# Sheet2.net
KiCad netlist of a schematic drawn in Altium Designer
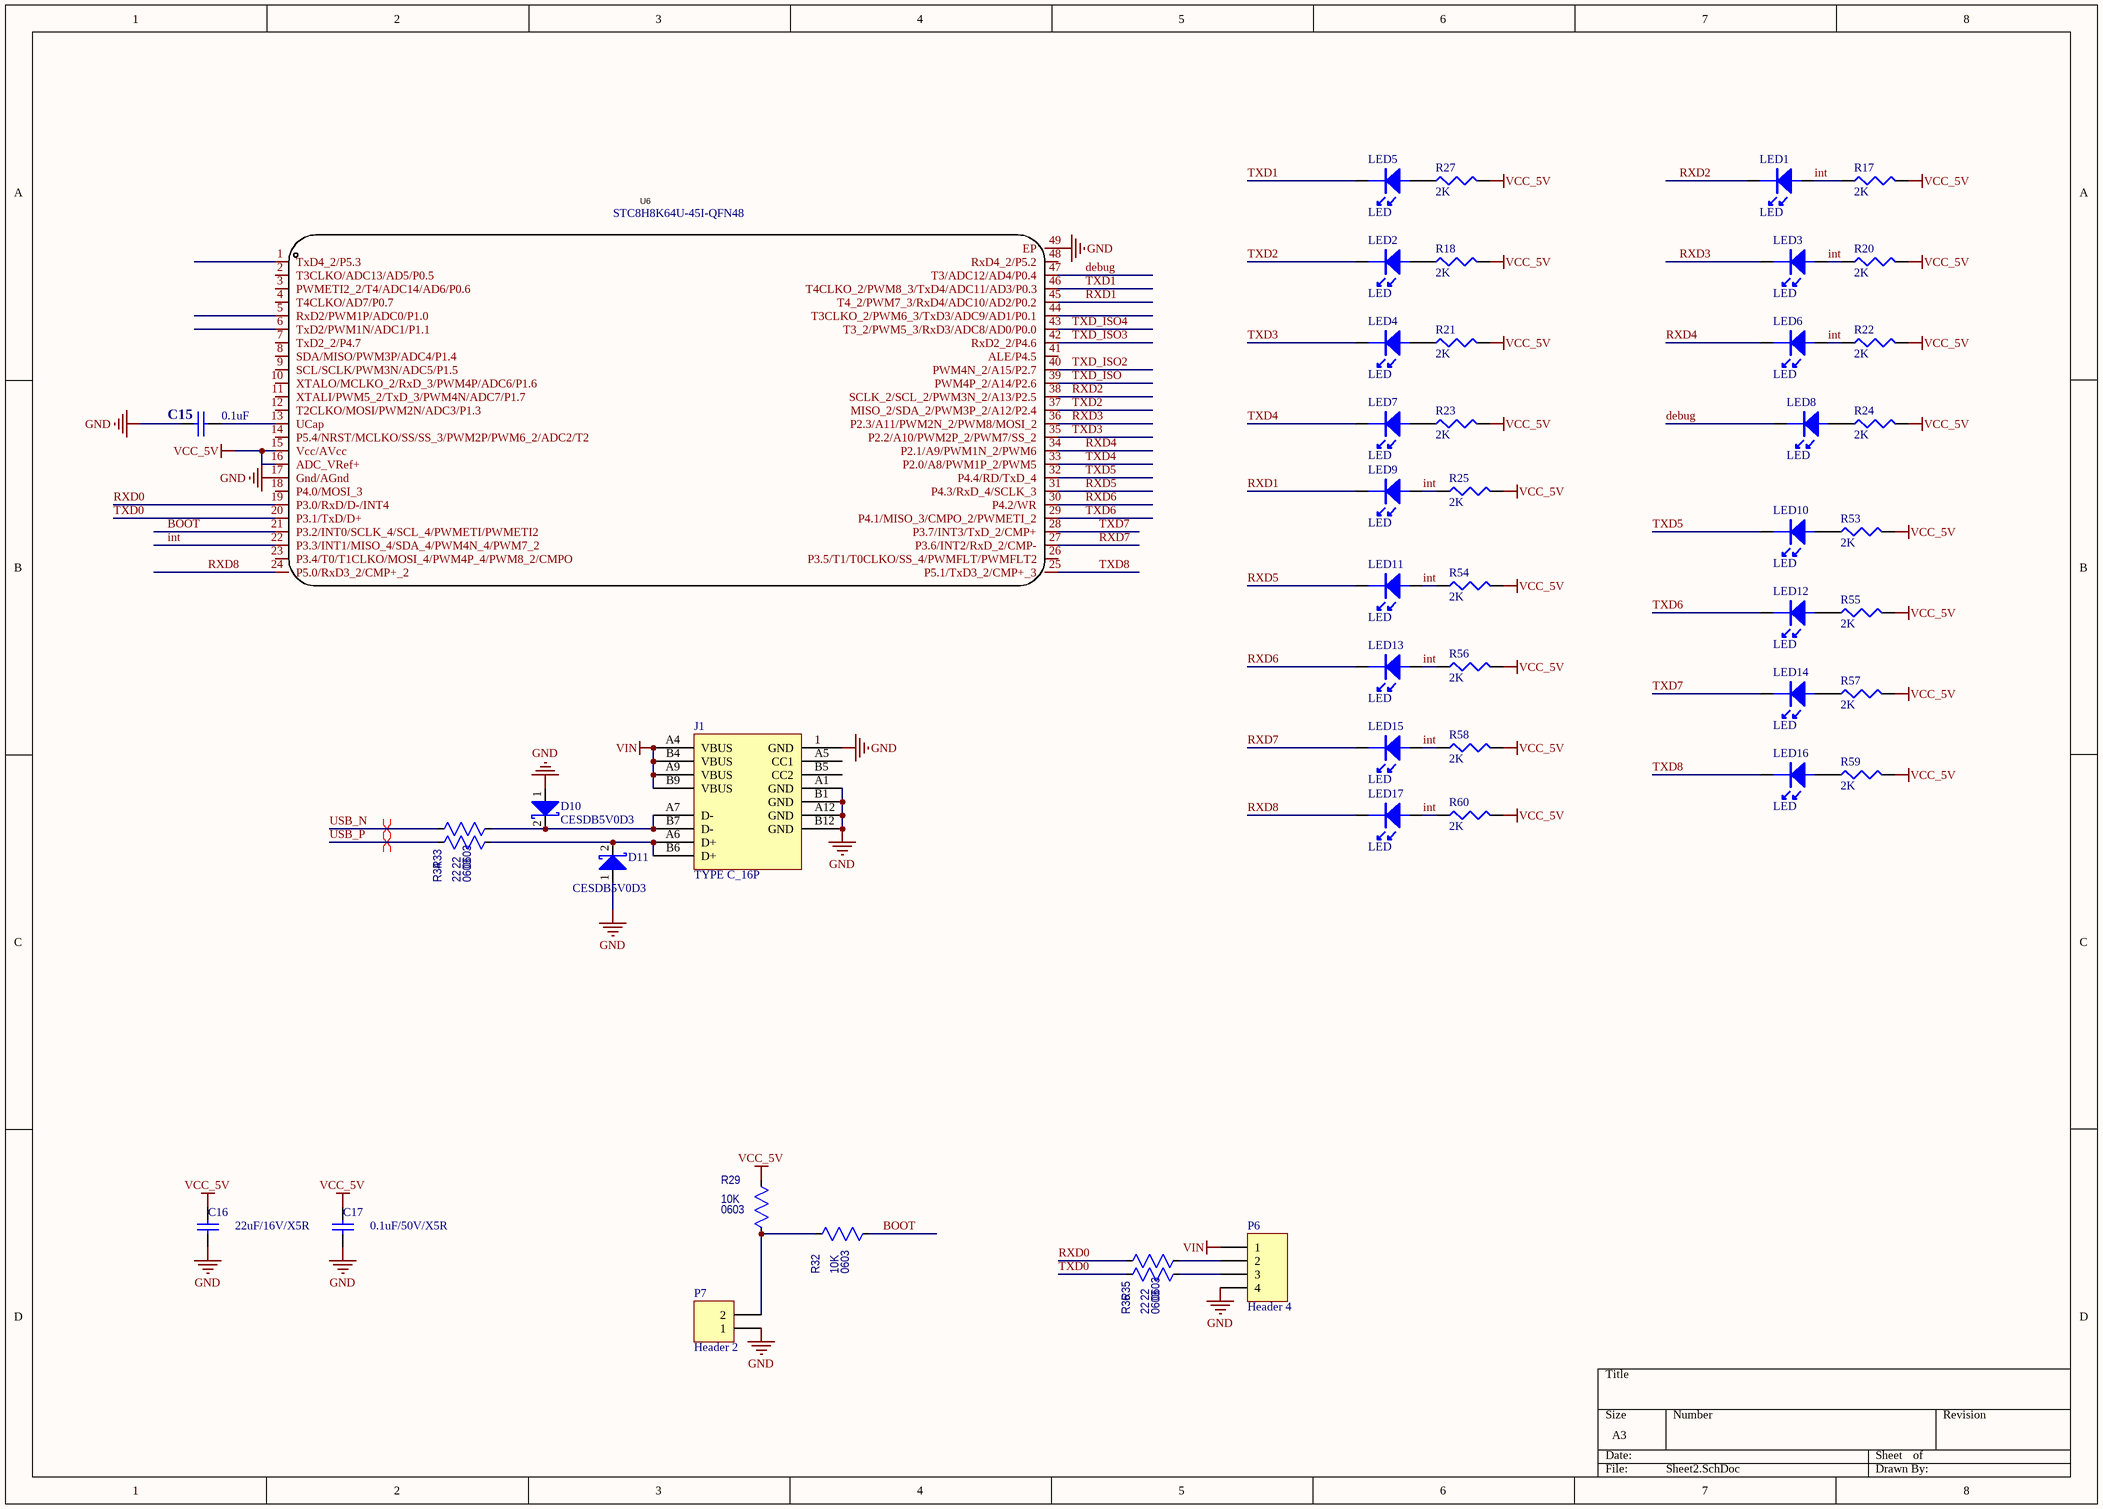
[diagram p0: Sheet2.SchDoc]

(export (version "E")
  (design (tool "Eeschema 10.0.6"))
  (components
    (comp (ref "C15")
      (value "0.1uF")
      (footprint "0603C")
      (description "Capacitor")
      (libsource (lib "*") (part "CAP"))
    )
    (comp (ref "C16")
      (value "22uF/16V/X5R")
      (footprint "0805C")
      (description "贴片电容 20%")
      (libsource (lib "XiaoyI") (part "CAP4"))
    )
    (comp (ref "C17")
      (value "0.1uF/50V/X5R")
      (footprint "0603C")
      (description "贴片电容 20%")
      (libsource (lib "XiaoyI") (part "CAP4"))
    )
    (comp (ref "D10")
      (value "CESDB5V0D3")
      (footprint "SOD323")
      (description "Schottky Diode")
      (libsource (lib "*") (part "DIODE S"))
    )
    (comp (ref "D11")
      (value "CESDB5V0D3")
      (footprint "SOD323")
      (description "Schottky Diode")
      (libsource (lib "*") (part "DIODE S"))
    )
    (comp (ref "J1")
      (value "TYPE C_16P")
      (footprint "TYPEC_16P")
      (libsource (lib "Schlib_20110825") (part "TYPE C_16P"))
    )
    (comp (ref "LED1") (value "LED") (footprint "0603LED") (libsource (lib "我的元件库") (part "LED")))
    (comp (ref "LED2") (value "LED") (footprint "0603LED") (libsource (lib "我的元件库") (part "LED")))
    (comp (ref "LED3") (value "LED") (footprint "0603LED") (libsource (lib "我的元件库") (part "LED")))
    (comp (ref "LED4") (value "LED") (footprint "0603LED") (libsource (lib "我的元件库") (part "LED")))
    (comp (ref "LED5") (value "LED") (footprint "0603LED") (libsource (lib "我的元件库") (part "LED")))
    (comp (ref "LED6") (value "LED") (footprint "0603LED") (libsource (lib "我的元件库") (part "LED")))
    (comp (ref "LED7") (value "LED") (footprint "0603LED") (libsource (lib "我的元件库") (part "LED")))
    (comp (ref "LED8") (value "LED") (footprint "0603LED") (libsource (lib "我的元件库") (part "LED")))
    (comp (ref "LED9") (value "LED") (footprint "0603LED") (libsource (lib "我的元件库") (part "LED")))
    (comp (ref "LED10") (value "LED") (footprint "0603LED") (libsource (lib "我的元件库") (part "LED")))
    (comp (ref "LED11") (value "LED") (footprint "0603LED") (libsource (lib "我的元件库") (part "LED")))
    (comp (ref "LED12") (value "LED") (footprint "0603LED") (libsource (lib "我的元件库") (part "LED")))
    (comp (ref "LED13") (value "LED") (footprint "0603LED") (libsource (lib "我的元件库") (part "LED")))
    (comp (ref "LED14") (value "LED") (footprint "0603LED") (libsource (lib "我的元件库") (part "LED")))
    (comp (ref "LED15") (value "LED") (footprint "0603LED") (libsource (lib "我的元件库") (part "LED")))
    (comp (ref "LED16") (value "LED") (footprint "0603LED") (libsource (lib "我的元件库") (part "LED")))
    (comp (ref "LED17") (value "LED") (footprint "0603LED") (libsource (lib "我的元件库") (part "LED")))
    (comp (ref "P6")
      (value "Header 4")
      (footprint "HDR1X4")
      (description "Header, 4-Pin")
      (fields (field (name "PUBLISHER") "Altium Limited"))
      (libsource (lib "Miscellaneous Connectors") (part "Header 4"))
    )
    (comp (ref "P7")
      (value "Header 2")
      (footprint "HDR1X2")
      (description "Header, 2-Pin")
      (fields (field (name "PUBLISHER") "Altium Limited"))
      (libsource (lib "Miscellaneous Connectors") (part "Header 2"))
    )
    (comp (ref "R17")
      (value "2K")
      (footprint "0603R")
      (libsource (lib "ZWLIntegrated_Library") (part "RES1"))
    )
    (comp (ref "R18")
      (value "2K")
      (footprint "0603R")
      (libsource (lib "ZWLIntegrated_Library") (part "RES1"))
    )
    (comp (ref "R20")
      (value "2K")
      (footprint "0603R")
      (libsource (lib "ZWLIntegrated_Library") (part "RES1"))
    )
    (comp (ref "R21")
      (value "2K")
      (footprint "0603R")
      (libsource (lib "ZWLIntegrated_Library") (part "RES1"))
    )
    (comp (ref "R22")
      (value "2K")
      (footprint "0603R")
      (libsource (lib "ZWLIntegrated_Library") (part "RES1"))
    )
    (comp (ref "R23")
      (value "2K")
      (footprint "0603R")
      (libsource (lib "ZWLIntegrated_Library") (part "RES1"))
    )
    (comp (ref "R24")
      (value "2K")
      (footprint "0603R")
      (libsource (lib "ZWLIntegrated_Library") (part "RES1"))
    )
    (comp (ref "R25")
      (value "2K")
      (footprint "0603R")
      (libsource (lib "ZWLIntegrated_Library") (part "RES1"))
    )
    (comp (ref "R27")
      (value "2K")
      (footprint "0603R")
      (libsource (lib "ZWLIntegrated_Library") (part "RES1"))
    )
    (comp (ref "R29")
      (value "10K")
      (footprint "0603r")
      (fields
        (field (name "PARTNUMBER") "RC0603FR-071KL")
        (field (name "TOLERANCE") "tol")
        (field (name "PACKAGE") "0603")
        (field (name "Comment") "10k")
      )
      (libsource (lib "Karl") (part "Resistor_0603"))
    )
    (comp (ref "R32")
      (value "10K")
      (footprint "0603r")
      (fields
        (field (name "PARTNUMBER") "RC0603FR-071KL")
        (field (name "TOLERANCE") "tol")
        (field (name "PACKAGE") "0603")
        (field (name "Comment") "10k")
      )
      (libsource (lib "Karl") (part "Resistor_0603"))
    )
    (comp (ref "R33")
      (value "22")
      (footprint "0603r")
      (fields
        (field (name "PARTNUMBER") "RC0603FR-071KL")
        (field (name "TOLERANCE") "tol")
        (field (name "PACKAGE") "0603")
        (field (name "Comment") "10k")
      )
      (libsource (lib "Karl") (part "Resistor_0603"))
    )
    (comp (ref "R34")
      (value "22")
      (footprint "0603r")
      (fields
        (field (name "PARTNUMBER") "RC0603FR-071KL")
        (field (name "TOLERANCE") "tol")
        (field (name "PACKAGE") "0603")
        (field (name "Comment") "10k")
      )
      (libsource (lib "Karl") (part "Resistor_0603"))
    )
    (comp (ref "R35")
      (value "22")
      (footprint "0603r")
      (fields
        (field (name "PARTNUMBER") "RC0603FR-071KL")
        (field (name "TOLERANCE") "tol")
        (field (name "PACKAGE") "0603")
        (field (name "Comment") "10k")
      )
      (libsource (lib "Karl") (part "Resistor_0603"))
    )
    (comp (ref "R36")
      (value "22")
      (footprint "0603r")
      (fields
        (field (name "PARTNUMBER") "RC0603FR-071KL")
        (field (name "TOLERANCE") "tol")
        (field (name "PACKAGE") "0603")
        (field (name "Comment") "10k")
      )
      (libsource (lib "Karl") (part "Resistor_0603"))
    )
    (comp (ref "R53")
      (value "2K")
      (footprint "0603R")
      (libsource (lib "ZWLIntegrated_Library") (part "RES1"))
    )
    (comp (ref "R54")
      (value "2K")
      (footprint "0603R")
      (libsource (lib "ZWLIntegrated_Library") (part "RES1"))
    )
    (comp (ref "R55")
      (value "2K")
      (footprint "0603R")
      (libsource (lib "ZWLIntegrated_Library") (part "RES1"))
    )
    (comp (ref "R56")
      (value "2K")
      (footprint "0603R")
      (libsource (lib "ZWLIntegrated_Library") (part "RES1"))
    )
    (comp (ref "R57")
      (value "2K")
      (footprint "0603R")
      (libsource (lib "ZWLIntegrated_Library") (part "RES1"))
    )
    (comp (ref "R58")
      (value "2K")
      (footprint "0603R")
      (libsource (lib "ZWLIntegrated_Library") (part "RES1"))
    )
    (comp (ref "R59")
      (value "2K")
      (footprint "0603R")
      (libsource (lib "ZWLIntegrated_Library") (part "RES1"))
    )
    (comp (ref "R60")
      (value "2K")
      (footprint "0603R")
      (libsource (lib "ZWLIntegrated_Library") (part "RES1"))
    )
    (comp (ref "U6")
      (value "STC8H8K64U-45I-QFN48")
      (footprint "QFN-48_L6.0-W6.0-P0.40-TL-EP4.4")
      (libsource (lib "altium-import") (part "root_0_STC8H8K64U-45I-QFN48_"))
    )
  )
  (nets
    (net (code "1") (name "/BOOT") (class "Default")
      (node (ref "R32") (pin "2") (pinfunction "2_2") (pintype "passive"))
      (node (ref "U6") (pin "21") (pinfunction "P3.2/INT0/SCLK_4/SCL_4/PWMETI/PWMETI2_21") (pintype "passive"))
    )
    (net (code "2") (name "/RXD0") (class "Default")
      (node (ref "R35") (pin "1") (pinfunction "1_1") (pintype "passive"))
      (node (ref "U6") (pin "19") (pinfunction "P3.0/RxD/D-/INT4_19") (pintype "passive"))
    )
    (net (code "3") (name "/RXD1") (class "Default")
      (node (ref "LED9") (pin "2") (pinfunction "2_2") (pintype "passive"))
      (node (ref "U6") (pin "45") (pinfunction "T4_2/PWM7_3/RxD4/ADC10/AD2/P0.2_45") (pintype "passive"))
    )
    (net (code "4") (name "/RXD2") (class "Default")
      (node (ref "LED1") (pin "2") (pinfunction "2_2") (pintype "passive"))
      (node (ref "U6") (pin "38") (pinfunction "SCLK_2/SCL_2/PWM3N_2/A13/P2.5_38") (pintype "passive"))
    )
    (net (code "5") (name "/RXD3") (class "Default")
      (node (ref "LED3") (pin "2") (pinfunction "2_2") (pintype "passive"))
      (node (ref "U6") (pin "36") (pinfunction "P2.3/A11/PWM2N_2/PWM8/MOSI_2_36") (pintype "passive"))
    )
    (net (code "6") (name "/RXD4") (class "Default")
      (node (ref "LED6") (pin "2") (pinfunction "2_2") (pintype "passive"))
      (node (ref "U6") (pin "34") (pinfunction "P2.1/A9/PWM1N_2/PWM6_34") (pintype "passive"))
    )
    (net (code "7") (name "/RXD5") (class "Default")
      (node (ref "LED11") (pin "2") (pinfunction "2_2") (pintype "passive"))
      (node (ref "U6") (pin "31") (pinfunction "P4.3/RxD_4/SCLK_3_31") (pintype "passive"))
    )
    (net (code "8") (name "/RXD6") (class "Default")
      (node (ref "LED13") (pin "2") (pinfunction "2_2") (pintype "passive"))
      (node (ref "U6") (pin "30") (pinfunction "P4.2/WR_30") (pintype "passive"))
    )
    (net (code "9") (name "/RXD7") (class "Default")
      (node (ref "LED15") (pin "2") (pinfunction "2_2") (pintype "passive"))
      (node (ref "U6") (pin "27") (pinfunction "P3.6/INT2/RxD_2/CMP-_27") (pintype "passive"))
    )
    (net (code "10") (name "/RXD8") (class "Default")
      (node (ref "LED17") (pin "2") (pinfunction "2_2") (pintype "passive"))
      (node (ref "U6") (pin "24") (pinfunction "P5.0/RxD3_2/CMP+_2_24") (pintype "passive"))
    )
    (net (code "11") (name "/TXD0") (class "Default")
      (node (ref "R36") (pin "1") (pinfunction "1_1") (pintype "passive"))
      (node (ref "U6") (pin "20") (pinfunction "P3.1/TxD/D+_20") (pintype "passive"))
    )
    (net (code "12") (name "/TXD1") (class "Default")
      (node (ref "LED5") (pin "2") (pinfunction "2_2") (pintype "passive"))
      (node (ref "U6") (pin "46") (pinfunction "T4CLKO_2/PWM8_3/TxD4/ADC11/AD3/P0.3_46") (pintype "passive"))
    )
    (net (code "13") (name "/TXD2") (class "Default")
      (node (ref "LED2") (pin "2") (pinfunction "2_2") (pintype "passive"))
      (node (ref "U6") (pin "37") (pinfunction "MISO_2/SDA_2/PWM3P_2/A12/P2.4_37") (pintype "passive"))
    )
    (net (code "14") (name "/TXD3") (class "Default")
      (node (ref "LED4") (pin "2") (pinfunction "2_2") (pintype "passive"))
      (node (ref "U6") (pin "35") (pinfunction "P2.2/A10/PWM2P_2/PWM7/SS_2_35") (pintype "passive"))
    )
    (net (code "15") (name "/TXD4") (class "Default")
      (node (ref "LED7") (pin "2") (pinfunction "2_2") (pintype "passive"))
      (node (ref "U6") (pin "33") (pinfunction "P2.0/A8/PWM1P_2/PWM5_33") (pintype "passive"))
    )
    (net (code "16") (name "/TXD5") (class "Default")
      (node (ref "LED10") (pin "2") (pinfunction "2_2") (pintype "passive"))
      (node (ref "U6") (pin "32") (pinfunction "P4.4/RD/TxD_4_32") (pintype "passive"))
    )
    (net (code "17") (name "/TXD6") (class "Default")
      (node (ref "LED12") (pin "2") (pinfunction "2_2") (pintype "passive"))
      (node (ref "U6") (pin "29") (pinfunction "P4.1/MISO_3/CMPO_2/PWMETI_2_29") (pintype "passive"))
    )
    (net (code "18") (name "/TXD7") (class "Default")
      (node (ref "LED14") (pin "2") (pinfunction "2_2") (pintype "passive"))
      (node (ref "U6") (pin "28") (pinfunction "P3.7/INT3/TxD_2/CMP+_28") (pintype "passive"))
    )
    (net (code "19") (name "/TXD8") (class "Default")
      (node (ref "LED16") (pin "2") (pinfunction "2_2") (pintype "passive"))
      (node (ref "U6") (pin "25") (pinfunction "P5.1/TxD3_2/CMP+_3_25") (pintype "passive"))
    )
    (net (code "20") (name "/TXD_ISO") (class "Default")
      (node (ref "U6") (pin "39") (pinfunction "PWM4P_2/A14/P2.6_39") (pintype "passive"))
    )
    (net (code "21") (name "/TXD_ISO2") (class "Default")
      (node (ref "U6") (pin "40") (pinfunction "PWM4N_2/A15/P2.7_40") (pintype "passive"))
    )
    (net (code "22") (name "/TXD_ISO3") (class "Default")
      (node (ref "U6") (pin "42") (pinfunction "RxD2_2/P4.6_42") (pintype "passive"))
    )
    (net (code "23") (name "/TXD_ISO4") (class "Default")
      (node (ref "U6") (pin "43") (pinfunction "T3_2/PWM5_3/RxD3/ADC8/AD0/P0.0_43") (pintype "passive"))
    )
    (net (code "24") (name "/USB_N") (class "Default")
      (node (ref "R33") (pin "1") (pinfunction "1_1") (pintype "passive"))
    )
    (net (code "25") (name "/USB_P") (class "Default")
      (node (ref "R34") (pin "1") (pinfunction "1_1") (pintype "passive"))
    )
    (net (code "26") (name "/debug") (class "Default")
      (node (ref "LED8") (pin "2") (pinfunction "2_2") (pintype "passive"))
      (node (ref "U6") (pin "47") (pinfunction "T3/ADC12/AD4/P0.4_47") (pintype "passive"))
    )
    (net (code "27") (name "/int") (class "Default")
      (node (ref "LED1") (pin "1") (pinfunction "1_1") (pintype "passive"))
      (node (ref "LED11") (pin "1") (pinfunction "1_1") (pintype "passive"))
      (node (ref "LED13") (pin "1") (pinfunction "1_1") (pintype "passive"))
      (node (ref "LED15") (pin "1") (pinfunction "1_1") (pintype "passive"))
      (node (ref "LED17") (pin "1") (pinfunction "1_1") (pintype "passive"))
      (node (ref "LED3") (pin "1") (pinfunction "1_1") (pintype "passive"))
      (node (ref "LED6") (pin "1") (pinfunction "1_1") (pintype "passive"))
      (node (ref "LED9") (pin "1") (pinfunction "1_1") (pintype "passive"))
      (node (ref "R17") (pin "1") (pinfunction "1_1") (pintype "passive"))
      (node (ref "R20") (pin "1") (pinfunction "1_1") (pintype "passive"))
      (node (ref "R22") (pin "1") (pinfunction "1_1") (pintype "passive"))
      (node (ref "R25") (pin "1") (pinfunction "1_1") (pintype "passive"))
      (node (ref "R54") (pin "1") (pinfunction "1_1") (pintype "passive"))
      (node (ref "R56") (pin "1") (pinfunction "1_1") (pintype "passive"))
      (node (ref "R58") (pin "1") (pinfunction "1_1") (pintype "passive"))
      (node (ref "R60") (pin "1") (pinfunction "1_1") (pintype "passive"))
      (node (ref "U6") (pin "22") (pinfunction "P3.3/INT1/MISO_4/SDA_4/PWM4N_4/PWM7_2_22") (pintype "passive"))
    )
    (net (code "28") (name "GND") (class "Default")
      (node (ref "C15") (pin "1") (pinfunction "1_1") (pintype "passive"))
      (node (ref "C16") (pin "1") (pinfunction "1_1") (pintype "passive"))
      (node (ref "C17") (pin "1") (pinfunction "1_1") (pintype "passive"))
      (node (ref "D10") (pin "1") (pinfunction "A_1") (pintype "passive"))
      (node (ref "D11") (pin "1") (pinfunction "A_1") (pintype "passive"))
      (node (ref "J1") (pin "1") (pinfunction "GND_1") (pintype "passive"))
      (node (ref "J1") (pin "A1") (pinfunction "GND_A1") (pintype "passive"))
      (node (ref "J1") (pin "A12") (pinfunction "GND_A12") (pintype "passive"))
      (node (ref "J1") (pin "B1") (pinfunction "GND_B1") (pintype "passive"))
      (node (ref "J1") (pin "B12") (pinfunction "GND_B12") (pintype "passive"))
      (node (ref "P6") (pin "4") (pinfunction "4_4") (pintype "passive"))
      (node (ref "P7") (pin "1") (pinfunction "1_1") (pintype "passive"))
      (node (ref "U6") (pin "17") (pinfunction "Gnd/AGnd_17") (pintype "passive"))
      (node (ref "U6") (pin "49") (pinfunction "EP_49") (pintype "passive"))
    )
    (net (code "29") (name "Net-(D10-K)") (class "Default")
      (node (ref "D10") (pin "2") (pinfunction "K_2") (pintype "passive"))
      (node (ref "J1") (pin "A7") (pinfunction "D-_A7") (pintype "passive"))
      (node (ref "J1") (pin "B7") (pinfunction "D-_B7") (pintype "passive"))
      (node (ref "R33") (pin "2") (pinfunction "2_2") (pintype "passive"))
    )
    (net (code "30") (name "Net-(D11-K)") (class "Default")
      (node (ref "D11") (pin "2") (pinfunction "K_2") (pintype "passive"))
      (node (ref "J1") (pin "A6") (pinfunction "D+_A6") (pintype "passive"))
      (node (ref "J1") (pin "B6") (pinfunction "D+_B6") (pintype "passive"))
      (node (ref "R34") (pin "2") (pinfunction "2_2") (pintype "passive"))
    )
    (net (code "31") (name "Net-(LED2-Pad1)") (class "Default")
      (node (ref "LED2") (pin "1") (pinfunction "1_1") (pintype "passive"))
      (node (ref "R18") (pin "1") (pinfunction "1_1") (pintype "passive"))
    )
    (net (code "32") (name "Net-(LED4-Pad1)") (class "Default")
      (node (ref "LED4") (pin "1") (pinfunction "1_1") (pintype "passive"))
      (node (ref "R21") (pin "1") (pinfunction "1_1") (pintype "passive"))
    )
    (net (code "33") (name "Net-(LED5-Pad1)") (class "Default")
      (node (ref "LED5") (pin "1") (pinfunction "1_1") (pintype "passive"))
      (node (ref "R27") (pin "1") (pinfunction "1_1") (pintype "passive"))
    )
    (net (code "34") (name "Net-(LED7-Pad1)") (class "Default")
      (node (ref "LED7") (pin "1") (pinfunction "1_1") (pintype "passive"))
      (node (ref "R23") (pin "1") (pinfunction "1_1") (pintype "passive"))
    )
    (net (code "35") (name "Net-(LED8-Pad1)") (class "Default")
      (node (ref "LED8") (pin "1") (pinfunction "1_1") (pintype "passive"))
      (node (ref "R24") (pin "1") (pinfunction "1_1") (pintype "passive"))
    )
    (net (code "36") (name "Net-(LED10-Pad1)") (class "Default")
      (node (ref "LED10") (pin "1") (pinfunction "1_1") (pintype "passive"))
      (node (ref "R53") (pin "1") (pinfunction "1_1") (pintype "passive"))
    )
    (net (code "37") (name "Net-(LED12-Pad1)") (class "Default")
      (node (ref "LED12") (pin "1") (pinfunction "1_1") (pintype "passive"))
      (node (ref "R55") (pin "1") (pinfunction "1_1") (pintype "passive"))
    )
    (net (code "38") (name "Net-(LED14-Pad1)") (class "Default")
      (node (ref "LED14") (pin "1") (pinfunction "1_1") (pintype "passive"))
      (node (ref "R57") (pin "1") (pinfunction "1_1") (pintype "passive"))
    )
    (net (code "39") (name "Net-(LED16-Pad1)") (class "Default")
      (node (ref "LED16") (pin "1") (pinfunction "1_1") (pintype "passive"))
      (node (ref "R59") (pin "1") (pinfunction "1_1") (pintype "passive"))
    )
    (net (code "40") (name "Net-(P6-Pad2)") (class "Default")
      (node (ref "P6") (pin "2") (pinfunction "2_2") (pintype "passive"))
      (node (ref "R35") (pin "2") (pinfunction "2_2") (pintype "passive"))
    )
    (net (code "41") (name "Net-(P6-Pad3)") (class "Default")
      (node (ref "P6") (pin "3") (pinfunction "3_3") (pintype "passive"))
      (node (ref "R36") (pin "2") (pinfunction "2_2") (pintype "passive"))
    )
    (net (code "42") (name "Net-(P7-Pad2)") (class "Default")
      (node (ref "P7") (pin "2") (pinfunction "2_2") (pintype "passive"))
      (node (ref "R29") (pin "2") (pinfunction "2_2") (pintype "passive"))
      (node (ref "R32") (pin "1") (pinfunction "1_1") (pintype "passive"))
    )
    (net (code "43") (name "Net-(U6-UCap)") (class "Default")
      (node (ref "C15") (pin "2") (pinfunction "2_2") (pintype "passive"))
      (node (ref "U6") (pin "13") (pinfunction "UCap_13") (pintype "passive"))
    )
    (net (code "44") (name "VCC_5V") (class "Default")
      (node (ref "C16") (pin "2") (pinfunction "2_2") (pintype "passive"))
      (node (ref "C17") (pin "2") (pinfunction "2_2") (pintype "passive"))
      (node (ref "R17") (pin "2") (pinfunction "2_2") (pintype "passive"))
      (node (ref "R18") (pin "2") (pinfunction "2_2") (pintype "passive"))
      (node (ref "R20") (pin "2") (pinfunction "2_2") (pintype "passive"))
      (node (ref "R21") (pin "2") (pinfunction "2_2") (pintype "passive"))
      (node (ref "R22") (pin "2") (pinfunction "2_2") (pintype "passive"))
      (node (ref "R23") (pin "2") (pinfunction "2_2") (pintype "passive"))
      (node (ref "R24") (pin "2") (pinfunction "2_2") (pintype "passive"))
      (node (ref "R25") (pin "2") (pinfunction "2_2") (pintype "passive"))
      (node (ref "R27") (pin "2") (pinfunction "2_2") (pintype "passive"))
      (node (ref "R29") (pin "1") (pinfunction "1_1") (pintype "passive"))
      (node (ref "R53") (pin "2") (pinfunction "2_2") (pintype "passive"))
      (node (ref "R54") (pin "2") (pinfunction "2_2") (pintype "passive"))
      (node (ref "R55") (pin "2") (pinfunction "2_2") (pintype "passive"))
      (node (ref "R56") (pin "2") (pinfunction "2_2") (pintype "passive"))
      (node (ref "R57") (pin "2") (pinfunction "2_2") (pintype "passive"))
      (node (ref "R58") (pin "2") (pinfunction "2_2") (pintype "passive"))
      (node (ref "R59") (pin "2") (pinfunction "2_2") (pintype "passive"))
      (node (ref "R60") (pin "2") (pinfunction "2_2") (pintype "passive"))
      (node (ref "U6") (pin "15") (pinfunction "Vcc/AVcc_15") (pintype "passive"))
      (node (ref "U6") (pin "16") (pinfunction "ADC_VRef+_16") (pintype "passive"))
    )
    (net (code "45") (name "VIN") (class "Default")
      (node (ref "J1") (pin "A4") (pinfunction "VBUS_A4") (pintype "passive"))
      (node (ref "J1") (pin "A9") (pinfunction "VBUS_A9") (pintype "passive"))
      (node (ref "J1") (pin "B4") (pinfunction "VBUS_B4") (pintype "passive"))
      (node (ref "J1") (pin "B9") (pinfunction "VBUS_B9") (pintype "passive"))
      (node (ref "P6") (pin "1") (pinfunction "1_1") (pintype "passive"))
    )
    (net (code "46") (name "unconnected-(J1-CC1-PadA5)") (class "Default")
      (node (ref "J1") (pin "A5") (pinfunction "CC1_A5") (pintype "passive"))
    )
    (net (code "47") (name "unconnected-(J1-CC2-PadB5)") (class "Default")
      (node (ref "J1") (pin "B5") (pinfunction "CC2_B5") (pintype "passive"))
    )
    (net (code "48") (name "unconnected-(U6-ALE{slash}P4.5-Pad41)") (class "Default")
      (node (ref "U6") (pin "41") (pinfunction "ALE/P4.5_41") (pintype "passive"))
    )
    (net (code "49") (name "unconnected-(U6-P3.4{slash}T0{slash}T1CLKO{slash}MOSI_4{slash}PWM4P_4{slash}PWM8_2{slash}CMPO-Pad23)") (class "Default")
      (node (ref "U6") (pin "23") (pinfunction "P3.4/T0/T1CLKO/MOSI_4/PWM4P_4/PWM8_2/CMPO_23") (pintype "passive"))
    )
    (net (code "50") (name "unconnected-(U6-P3.5{slash}T1{slash}T0CLKO{slash}SS_4{slash}PWMFLT{slash}PWMFLT2-Pad26)") (class "Default")
      (node (ref "U6") (pin "26") (pinfunction "P3.5/T1/T0CLKO/SS_4/PWMFLT/PWMFLT2_26") (pintype "passive"))
    )
    (net (code "51") (name "unconnected-(U6-P4.0{slash}MOSI_3-Pad18)") (class "Default")
      (node (ref "U6") (pin "18") (pinfunction "P4.0/MOSI_3_18") (pintype "passive"))
    )
    (net (code "52") (name "unconnected-(U6-P5.4{slash}NRST{slash}MCLKO{slash}SS{slash}SS_3{slash}PWM2P{slash}PWM6_2{slash}ADC2{slash}T2-Pad14)") (class "Default")
      (node (ref "U6") (pin "14") (pinfunction "P5.4/NRST/MCLKO/SS/SS_3/PWM2P/PWM6_2/ADC2/T2_14") (pintype "passive"))
    )
    (net (code "53") (name "unconnected-(U6-PWMETI2_2{slash}T4{slash}ADC14{slash}AD6{slash}P0.6-Pad3)") (class "Default")
      (node (ref "U6") (pin "3") (pinfunction "PWMETI2_2/T4/ADC14/AD6/P0.6_3") (pintype "passive"))
    )
    (net (code "54") (name "unconnected-(U6-RxD2{slash}PWM1P{slash}ADC0{slash}P1.0-Pad5)") (class "Default")
      (node (ref "U6") (pin "5") (pinfunction "RxD2/PWM1P/ADC0/P1.0_5") (pintype "passive"))
    )
    (net (code "55") (name "unconnected-(U6-RxD4_2{slash}P5.2-Pad48)") (class "Default")
      (node (ref "U6") (pin "48") (pinfunction "RxD4_2/P5.2_48") (pintype "passive"))
    )
    (net (code "56") (name "unconnected-(U6-SCL{slash}SCLK{slash}PWM3N{slash}ADC5{slash}P1.5-Pad9)") (class "Default")
      (node (ref "U6") (pin "9") (pinfunction "SCL/SCLK/PWM3N/ADC5/P1.5_9") (pintype "passive"))
    )
    (net (code "57") (name "unconnected-(U6-SDA{slash}MISO{slash}PWM3P{slash}ADC4{slash}P1.4-Pad8)") (class "Default")
      (node (ref "U6") (pin "8") (pinfunction "SDA/MISO/PWM3P/ADC4/P1.4_8") (pintype "passive"))
    )
    (net (code "58") (name "unconnected-(U6-T2CLKO{slash}MOSI{slash}PWM2N{slash}ADC3{slash}P1.3-Pad12)") (class "Default")
      (node (ref "U6") (pin "12") (pinfunction "T2CLKO/MOSI/PWM2N/ADC3/P1.3_12") (pintype "passive"))
    )
    (net (code "59") (name "unconnected-(U6-T3CLKO_2{slash}PWM6_3{slash}TxD3{slash}ADC9{slash}AD1{slash}P0.1-Pad44)") (class "Default")
      (node (ref "U6") (pin "44") (pinfunction "T3CLKO_2/PWM6_3/TxD3/ADC9/AD1/P0.1_44") (pintype "passive"))
    )
    (net (code "60") (name "unconnected-(U6-T3CLKO{slash}ADC13{slash}AD5{slash}P0.5-Pad2)") (class "Default")
      (node (ref "U6") (pin "2") (pinfunction "T3CLKO/ADC13/AD5/P0.5_2") (pintype "passive"))
    )
    (net (code "61") (name "unconnected-(U6-T4CLKO{slash}AD7{slash}P0.7-Pad4)") (class "Default")
      (node (ref "U6") (pin "4") (pinfunction "T4CLKO/AD7/P0.7_4") (pintype "passive"))
    )
    (net (code "62") (name "unconnected-(U6-TxD2_2{slash}P4.7-Pad7)") (class "Default")
      (node (ref "U6") (pin "7") (pinfunction "TxD2_2/P4.7_7") (pintype "passive"))
    )
    (net (code "63") (name "unconnected-(U6-TxD2{slash}PWM1N{slash}ADC1{slash}P1.1-Pad6)") (class "Default")
      (node (ref "U6") (pin "6") (pinfunction "TxD2/PWM1N/ADC1/P1.1_6") (pintype "passive"))
    )
    (net (code "64") (name "unconnected-(U6-TxD4_2{slash}P5.3-Pad1)") (class "Default")
      (node (ref "U6") (pin "1") (pinfunction "TxD4_2/P5.3_1") (pintype "passive"))
    )
    (net (code "65") (name "unconnected-(U6-XTALI{slash}PWM5_2{slash}TxD_3{slash}PWM4N{slash}ADC7{slash}P1.7-Pad11)") (class "Default")
      (node (ref "U6") (pin "11") (pinfunction "XTALI/PWM5_2/TxD_3/PWM4N/ADC7/P1.7_11") (pintype "passive"))
    )
    (net (code "66") (name "unconnected-(U6-XTALO{slash}MCLKO_2{slash}RxD_3{slash}PWM4P{slash}ADC6{slash}P1.6-Pad10)") (class "Default")
      (node (ref "U6") (pin "10") (pinfunction "XTALO/MCLKO_2/RxD_3/PWM4P/ADC6/P1.6_10") (pintype "passive"))
    )
  )
)
